# PSU.net
KiCad netlist of a schematic drawn in Altium Designer
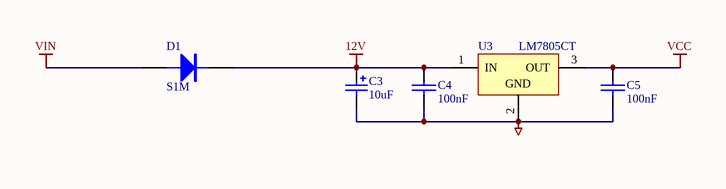
[diagram p0: PSU.SchDoc]

(export (version "E")
  (design (tool "Eeschema 10.0.6"))
  (components
    (comp (ref "C3")
      (value "10uF")
      (footprint "TAG B CASE")
      (description "CAPACITOR POLARISED TAG B CASE")
      (fields
        (field (name "MANUFACTURER") "Vishay/Sprague")
        (field (name "MOUSER PART NO.") "71-591D106X9020B2T15")
      )
      (libsource (lib "Mi-Call Schematic") (part "Cap Pol"))
    )
    (comp (ref "C4")
      (value "100nF")
      (footprint "CAP (3D) - 0603")
      (description "CAPACITOR SMD 0603")
      (fields (field (name "MOUSER PART NO.") "81-GCM188R71C104KA7D") (field (name "MANUFACTURER") "Murata"))
      (libsource (lib "Mi-Call Schematic") (part "CAP"))
    )
    (comp (ref "C5")
      (value "100nF")
      (footprint "CAP (3D) - 0603")
      (description "CAPACITOR SMD 0603")
      (fields (field (name "MOUSER PART NO.") "81-GCM188R71C104KA7D") (field (name "MANUFACTURER") "Murata"))
      (libsource (lib "Mi-Call Schematic") (part "CAP"))
    )
    (comp (ref "D1")
      (value "S1M")
      (footprint "DO-214AC")
      (description "DIODE, POWER")
      (fields (field (name "MOUSER PART NO.") "821-S1M") (field (name "MANUFACTURER") "TAIWAN SEMI"))
      (libsource (lib "*") (part "DIODE"))
    )
    (comp (ref "U3")
      (value "LM7805CT")
      (footprint "TO-220")
      (description "3-Terminal Positive Fixed Voltage Regulator")
      (fields
        (field (name "MOUSER PART NO.") "512-LM7805CT")
        (field (name "MANUFACTURER") "Fairchild Semiconductor")
      )
      (libsource (lib "Motorola Power Mgt Voltage Regulator") (part "MC7805ACT"))
    )
  )
  (nets
    (net (code "1") (name "12V") (class "Default")
      (node (ref "C3") (pin "1") (pinfunction "1_1") (pintype "passive"))
      (node (ref "C4") (pin "1") (pinfunction "1_1") (pintype "passive"))
      (node (ref "D1") (pin "2") (pinfunction "K_2") (pintype "passive"))
      (node (ref "U3") (pin "1") (pinfunction "IN_1") (pintype "power_in"))
    )
    (net (code "2") (name "GND") (class "Default")
      (node (ref "C3") (pin "2") (pinfunction "2_2") (pintype "passive"))
      (node (ref "C4") (pin "2") (pinfunction "2_2") (pintype "passive"))
      (node (ref "C5") (pin "2") (pinfunction "2_2") (pintype "passive"))
      (node (ref "U3") (pin "2") (pinfunction "GND_2") (pintype "power_in"))
    )
    (net (code "3") (name "VCC") (class "Default")
      (node (ref "C5") (pin "1") (pinfunction "1_1") (pintype "passive"))
      (node (ref "U3") (pin "3") (pinfunction "OUT_3") (pintype "power_in"))
    )
    (net (code "4") (name "VIN") (class "Default")
      (node (ref "D1") (pin "1") (pinfunction "A_1") (pintype "passive"))
    )
  )
)
